# v2_2_lux.net
KiCad netlist of a schematic drawn in EAGLE
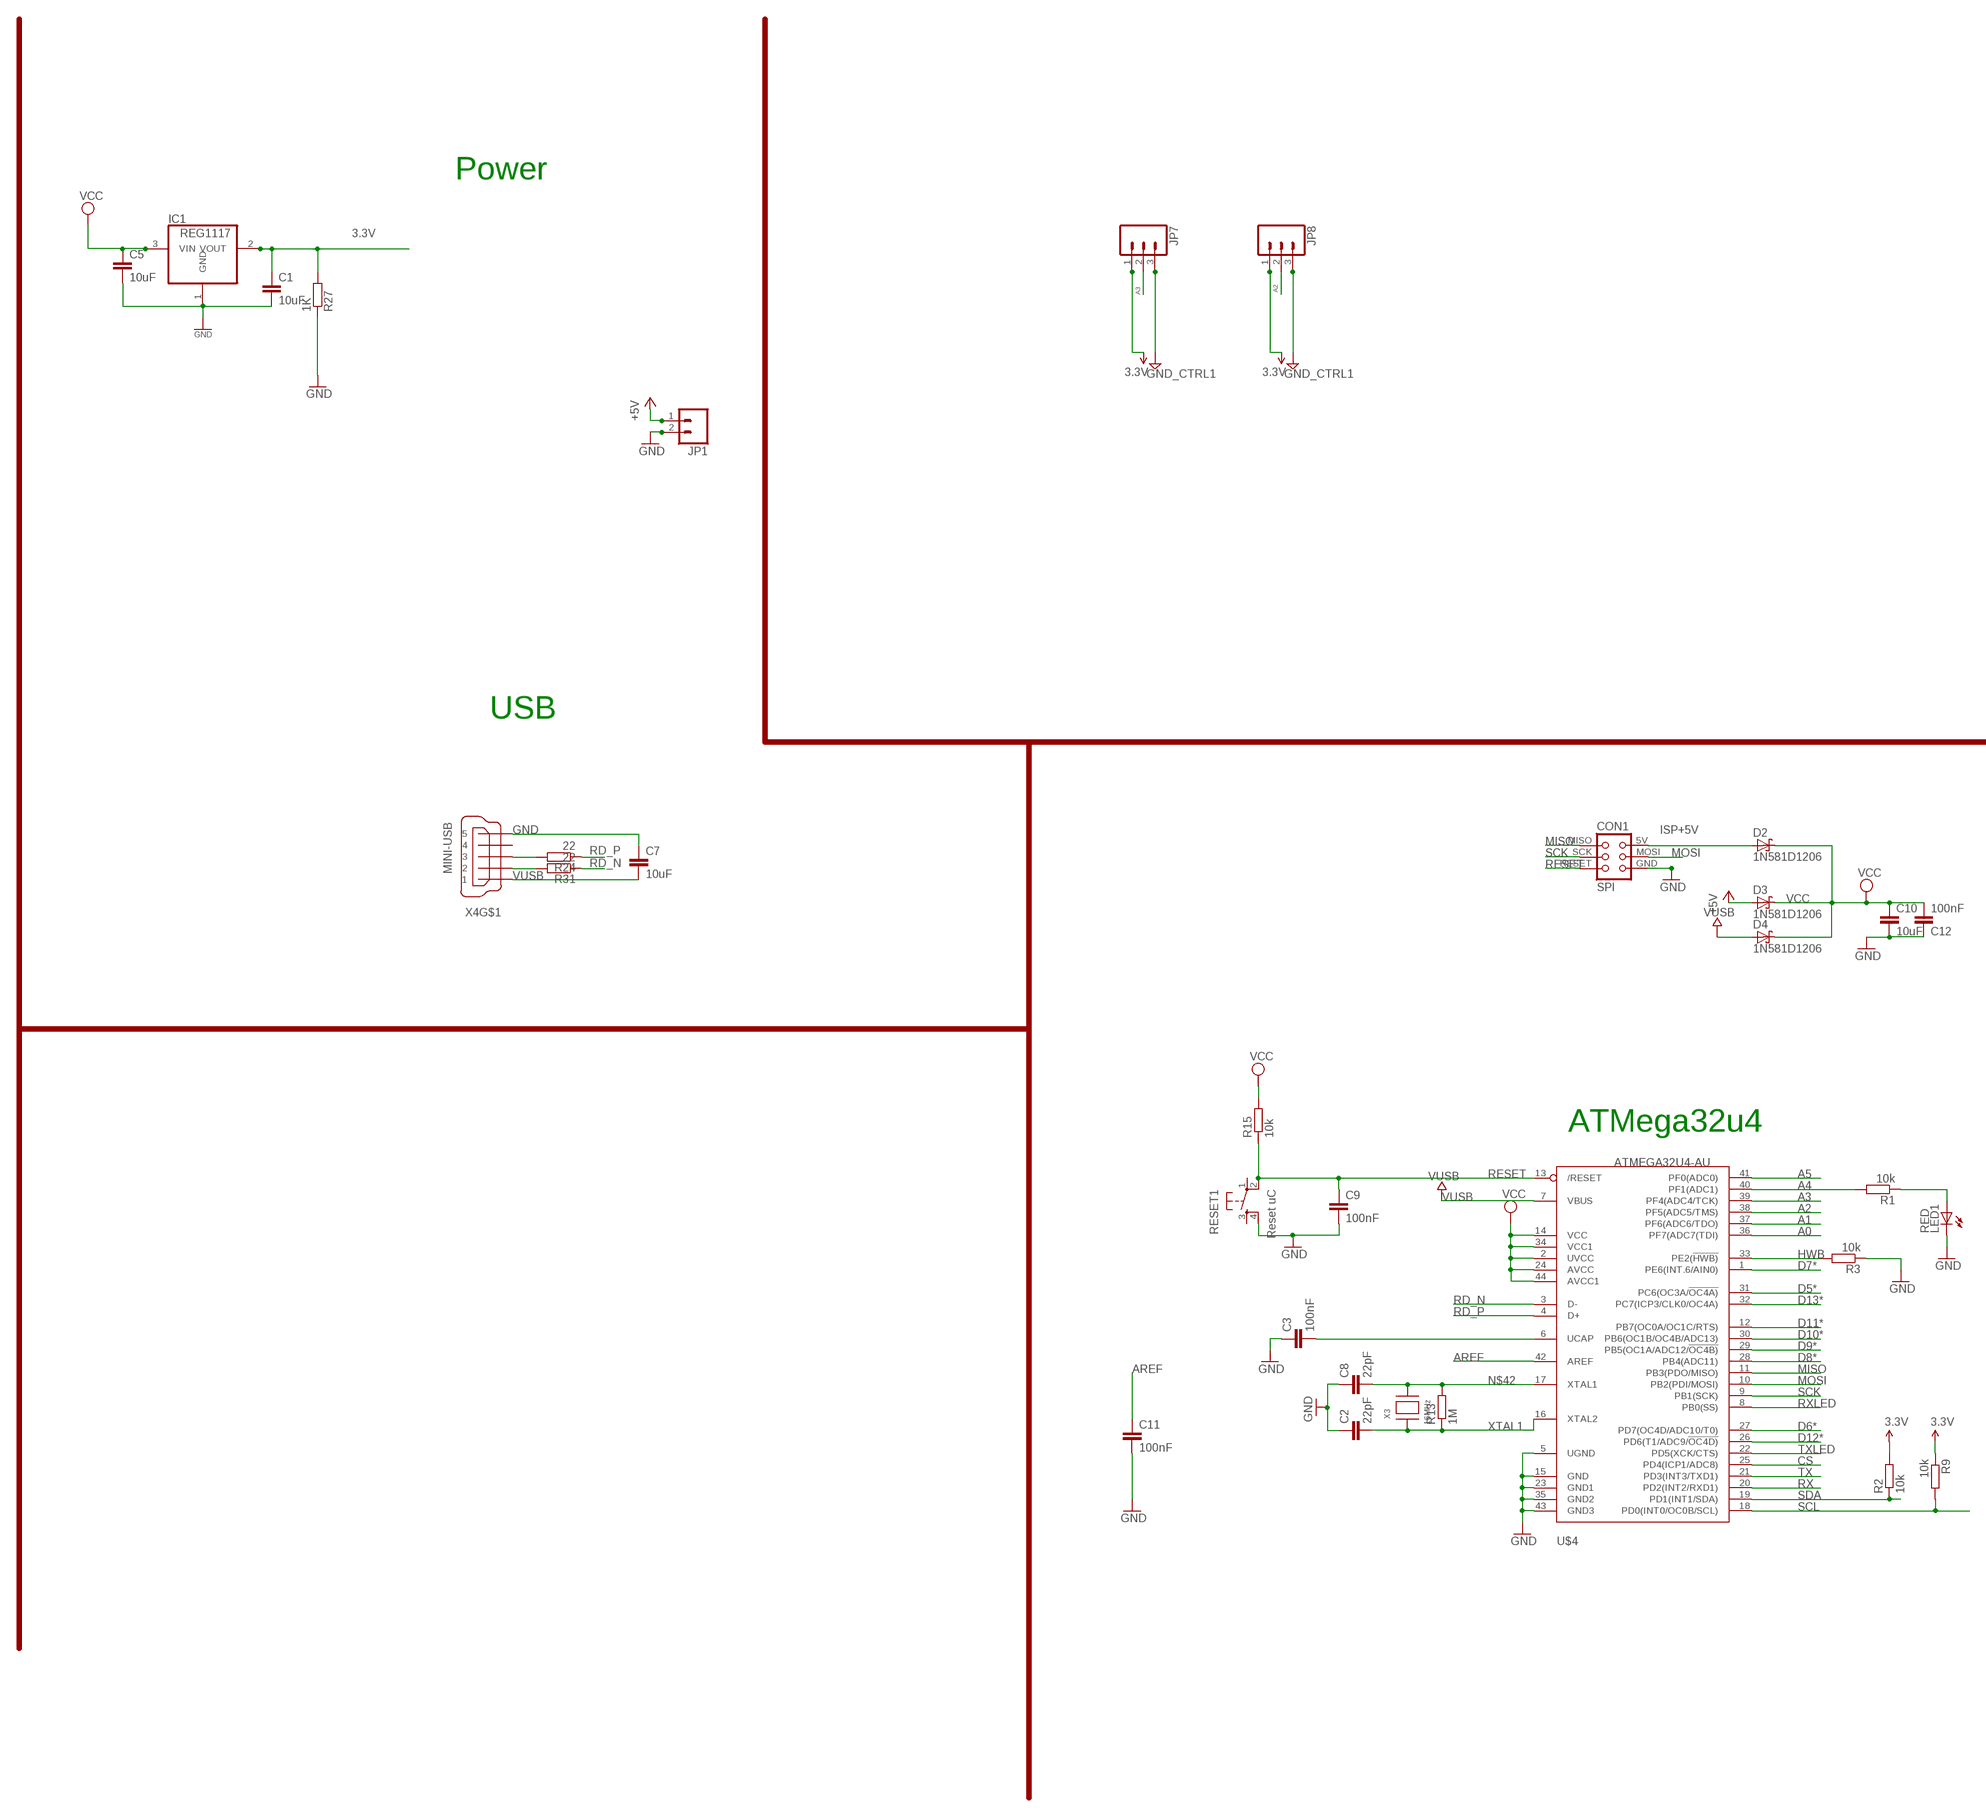
[diagram p0: schematic, sheet 1, part 1 of 2]
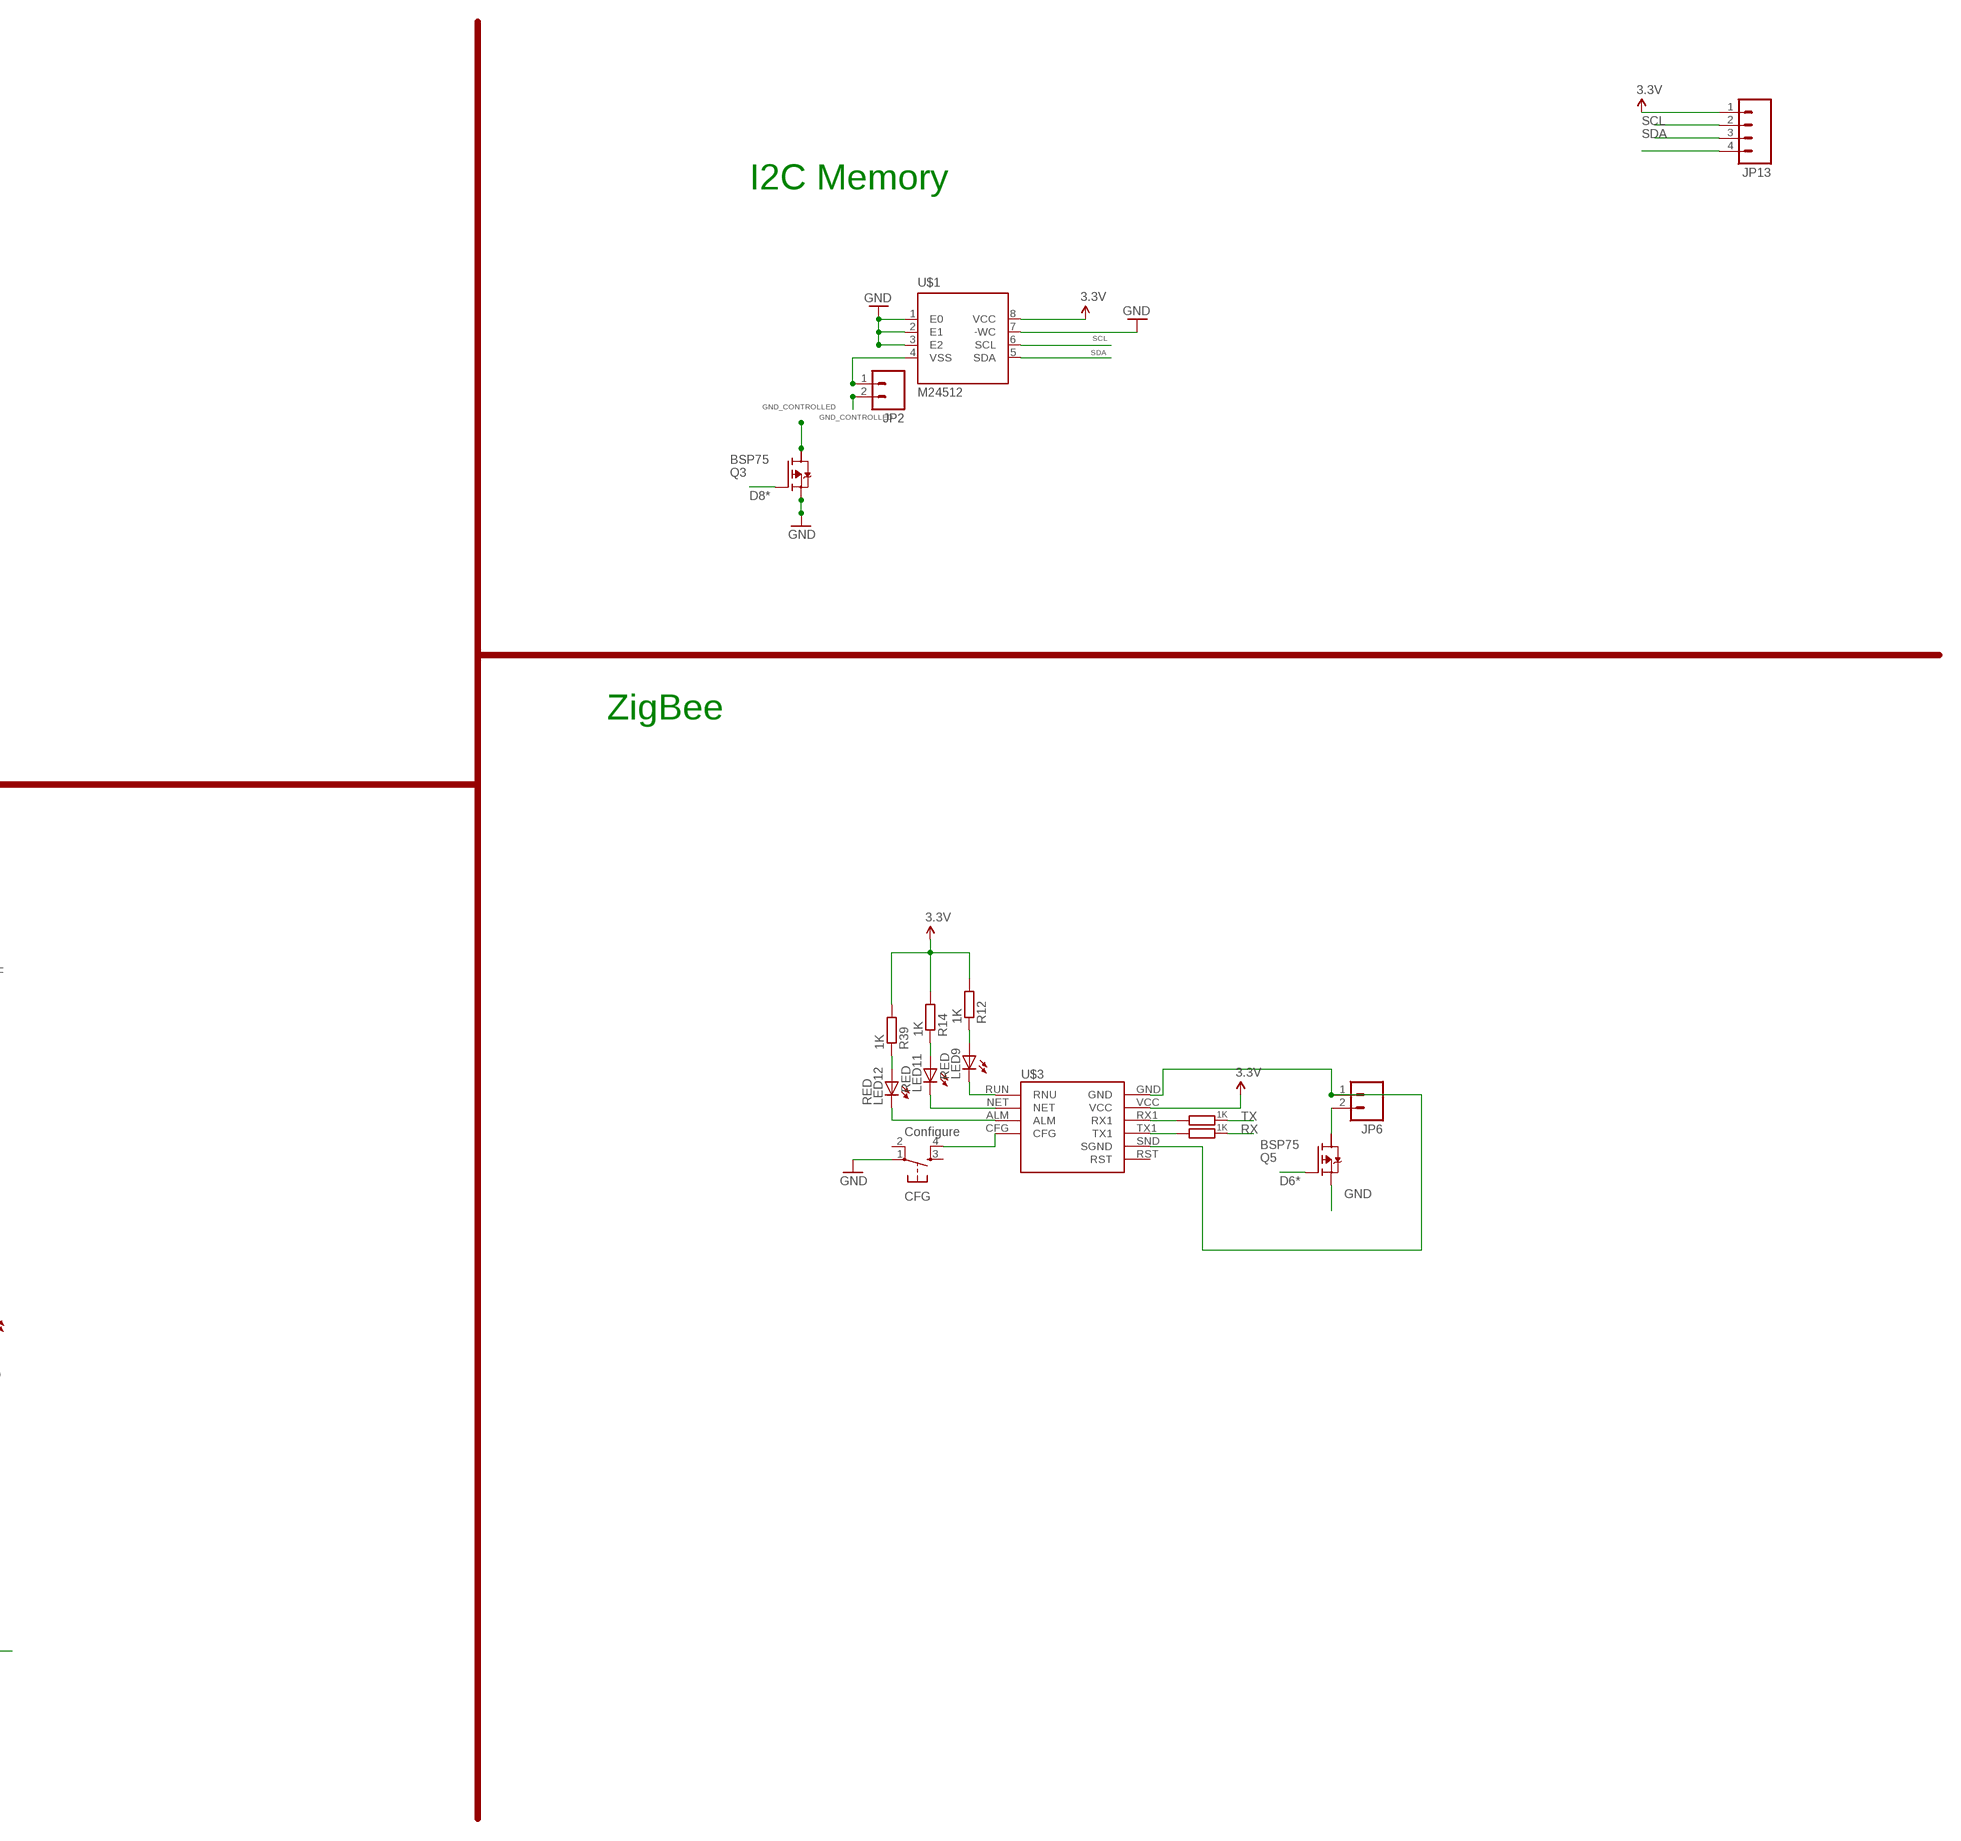
[diagram p1: schematic, sheet 1, part 2 of 2]

(export (version "E")
  (design (tool "Eeschema 10.0.6"))
  (components
    (comp (ref "C1")
      (value "10uF")
      (footprint "eagle-import:C1206")
      (libsource (lib "eagle-import") (part "C-EUC1206"))
    )
    (comp (ref "C2")
      (value "22pF")
      (footprint "eagle-import:C1206")
      (libsource (lib "eagle-import") (part "C-EUC1206"))
    )
    (comp (ref "C3")
      (value "100nF")
      (footprint "eagle-import:C1206")
      (libsource (lib "eagle-import") (part "C-EUC1206"))
    )
    (comp (ref "C5")
      (value "10uF")
      (footprint "eagle-import:C1206")
      (libsource (lib "eagle-import") (part "C-EUC1206"))
    )
    (comp (ref "C7")
      (value "10uF")
      (footprint "eagle-import:C1206")
      (libsource (lib "eagle-import") (part "C-EUC1206"))
    )
    (comp (ref "C8")
      (value "22pF")
      (footprint "eagle-import:C1206")
      (libsource (lib "eagle-import") (part "C-EUC1206"))
    )
    (comp (ref "C9")
      (value "100nF")
      (footprint "eagle-import:C1206")
      (libsource (lib "eagle-import") (part "C-EUC1206"))
    )
    (comp (ref "C10")
      (value "10uF")
      (footprint "eagle-import:C1206")
      (libsource (lib "eagle-import") (part "C-EUC1206"))
    )
    (comp (ref "C11")
      (value "100nF")
      (footprint "eagle-import:C1206")
      (libsource (lib "eagle-import") (part "C-EUC1206"))
    )
    (comp (ref "C12")
      (value "100nF")
      (footprint "eagle-import:C1206")
      (libsource (lib "eagle-import") (part "C-EUC1206"))
    )
    (comp (ref "CFG")
      (value "Configure")
      (footprint "eagle-import:TACTILE_SWITCH_SMD")
      (libsource (lib "eagle-import") (part "TAC_SWITCHSMD"))
    )
    (comp (ref "CON1")
      (value "SPI")
      (footprint "eagle-import:TC2030-MCP-NL")
      (libsource (lib "eagle-import") (part "TINYISPT"))
    )
    (comp (ref "D2")
      (value "1N581D1206")
      (footprint "eagle-import:LED-1206")
      (libsource (lib "eagle-import") (part "1N581D1206"))
    )
    (comp (ref "D3")
      (value "1N581D1206")
      (footprint "eagle-import:LED-1206")
      (libsource (lib "eagle-import") (part "1N581D1206"))
    )
    (comp (ref "D4")
      (value "1N581D1206")
      (footprint "eagle-import:LED-1206")
      (libsource (lib "eagle-import") (part "1N581D1206"))
    )
    (comp (ref "IC1")
      (value "REG1117")
      (footprint "eagle-import:SOT223")
      (libsource (lib "eagle-import") (part "REG1117"))
    )
    (comp (ref "JP1")
      (value "M02LOCK_LONGPADS")
      (footprint "eagle-import:1X02_LOCK_LONGPADS")
      (libsource (lib "eagle-import") (part "M02LOCK_LONGPADS"))
    )
    (comp (ref "JP2")
      (value "M02LOCK_LONGPADS")
      (footprint "eagle-import:1X02_LOCK_LONGPADS")
      (libsource (lib "eagle-import") (part "M02LOCK_LONGPADS"))
    )
    (comp (ref "JP6")
      (value "M02LOCK_LONGPADS")
      (footprint "eagle-import:1X02_LOCK_LONGPADS")
      (libsource (lib "eagle-import") (part "M02LOCK_LONGPADS"))
    )
    (comp (ref "JP7")
      (value "M03LONGPADS")
      (footprint "eagle-import:1X03_LONGPADS")
      (libsource (lib "eagle-import") (part "M03LONGPADS"))
    )
    (comp (ref "JP8")
      (value "M03LONGPADS")
      (footprint "eagle-import:1X03_LONGPADS")
      (libsource (lib "eagle-import") (part "M03LONGPADS"))
    )
    (comp (ref "JP13")
      (value "M04LOCK_LONGPADS")
      (footprint "eagle-import:1X04_LOCK_LONGPADS")
      (libsource (lib "eagle-import") (part "M04LOCK_LONGPADS"))
    )
    (comp (ref "LED1")
      (value "RED")
      (footprint "eagle-import:CHIP-LED0805")
      (libsource (lib "eagle-import") (part "LEDCHIP-LED0805"))
    )
    (comp (ref "LED9")
      (value "RED")
      (footprint "eagle-import:CHIP-LED0805")
      (libsource (lib "eagle-import") (part "LEDCHIP-LED0805"))
    )
    (comp (ref "LED11")
      (value "RED")
      (footprint "eagle-import:CHIP-LED0805")
      (libsource (lib "eagle-import") (part "LEDCHIP-LED0805"))
    )
    (comp (ref "LED12")
      (value "RED")
      (footprint "eagle-import:CHIP-LED0805")
      (libsource (lib "eagle-import") (part "LEDCHIP-LED0805"))
    )
    (comp (ref "Q3")
      (value "BSP75")
      (footprint "eagle-import:PG-SOT-223")
      (libsource (lib "eagle-import") (part "BSP613P"))
    )
    (comp (ref "Q5")
      (value "BSP75")
      (footprint "eagle-import:PG-SOT-223")
      (libsource (lib "eagle-import") (part "BSP613P"))
    )
    (comp (ref "R1")
      (value "10k")
      (footprint "eagle-import:M1206")
      (libsource (lib "eagle-import") (part "resistor_R-EU_M1206"))
    )
    (comp (ref "R2")
      (value "10k")
      (footprint "eagle-import:M1206")
      (libsource (lib "eagle-import") (part "resistor_R-EU_M1206"))
    )
    (comp (ref "R3")
      (value "10k")
      (footprint "eagle-import:M1206")
      (libsource (lib "eagle-import") (part "resistor_R-EU_M1206"))
    )
    (comp (ref "R8")
      (value "1K")
      (footprint "eagle-import:R0805")
      (libsource (lib "eagle-import") (part "R-EU_R0805"))
    )
    (comp (ref "R9")
      (value "10k")
      (footprint "eagle-import:M1206")
      (libsource (lib "eagle-import") (part "resistor_R-EU_M1206"))
    )
    (comp (ref "R11")
      (value "1K")
      (footprint "eagle-import:R0805")
      (libsource (lib "eagle-import") (part "R-EU_R0805"))
    )
    (comp (ref "R12")
      (value "1K")
      (footprint "eagle-import:R0805")
      (libsource (lib "eagle-import") (part "R-EU_R0805"))
    )
    (comp (ref "R13")
      (value "1M")
      (footprint "eagle-import:R1206")
      (libsource (lib "eagle-import") (part "R-EU_R1206"))
    )
    (comp (ref "R14")
      (value "1K")
      (footprint "eagle-import:R0805")
      (libsource (lib "eagle-import") (part "R-EU_R0805"))
    )
    (comp (ref "R15")
      (value "10k")
      (footprint "eagle-import:M0805")
      (libsource (lib "eagle-import") (part "resistor_R-EU_M0805"))
    )
    (comp (ref "R24")
      (value "22")
      (footprint "eagle-import:M1206")
      (libsource (lib "eagle-import") (part "resistor_R-EU_M1206"))
    )
    (comp (ref "R27")
      (value "1K")
      (footprint "eagle-import:R0805")
      (libsource (lib "eagle-import") (part "R-EU_R0805"))
    )
    (comp (ref "R31")
      (value "22")
      (footprint "eagle-import:M1206")
      (libsource (lib "eagle-import") (part "resistor_R-EU_M1206"))
    )
    (comp (ref "R39")
      (value "1K")
      (footprint "eagle-import:R0805")
      (libsource (lib "eagle-import") (part "R-EU_R0805"))
    )
    (comp (ref "RESET1")
      (value "Reset uC")
      (footprint "eagle-import:TACTILE_SWITCH_SMD")
      (libsource (lib "eagle-import") (part "TAC_SWITCHSMD"))
    )
    (comp (ref "U$1")
      (value "M24512")
      (footprint "eagle-import:SO8")
      (libsource (lib "eagle-import") (part "M24512"))
    )
    (comp (ref "U$3")
      (value "SZ05-ZIGBEETHROUGHHOLE")
      (footprint "eagle-import:SZ05-ZIGBEE4")
      (libsource (lib "eagle-import") (part "SZ05-ZIGBEETHROUGHHOLE"))
    )
    (comp (ref "U$4")
      (value "ATMEGA32U4-AU")
      (footprint "eagle-import:TQFP44")
      (libsource (lib "eagle-import") (part "ATMEGA32U4-AU"))
    )
    (comp (ref "X3")
      (value "16MHz")
      (footprint "eagle-import:NX6035")
      (libsource (lib "eagle-import") (part "XTALNX6035"))
    )
    (comp (ref "X4")
      (value "MINI-USB")
      (footprint "eagle-import:32005-201")
      (libsource (lib "eagle-import") (part "MINI-USB-SCHIELD-32005-201"))
    )
  )
  (nets
    (net (code "1") (name "+5V") (class "Default")
      (node (ref "D3") (pin "A") (pinfunction "A_A") (pintype "passive"))
      (node (ref "JP1") (pin "1") (pinfunction "1_1") (pintype "passive"))
    )
    (net (code "2") (name "/A0") (class "Default")
      (node (ref "U$4") (pin "36") (pinfunction "PF7(ADC7(TDI)_36") (pintype "bidirectional"))
    )
    (net (code "3") (name "/A1") (class "Default")
      (node (ref "U$4") (pin "37") (pinfunction "PF6(ADC6/TDO)_37") (pintype "bidirectional"))
    )
    (net (code "4") (name "/A2") (class "Default")
      (node (ref "JP8") (pin "2") (pinfunction "2_2") (pintype "passive"))
      (node (ref "U$4") (pin "38") (pinfunction "PF5(ADC5/TMS)_38") (pintype "bidirectional"))
    )
    (net (code "5") (name "/A3") (class "Default")
      (node (ref "JP7") (pin "2") (pinfunction "2_2") (pintype "passive"))
      (node (ref "U$4") (pin "39") (pinfunction "PF4(ADC4/TCK)_39") (pintype "bidirectional"))
    )
    (net (code "6") (name "/A4") (class "Default")
      (node (ref "R1") (pin "2") (pinfunction "2_2") (pintype "passive"))
      (node (ref "U$4") (pin "40") (pinfunction "PF1(ADC1)_40") (pintype "bidirectional"))
    )
    (net (code "7") (name "/A5") (class "Default")
      (node (ref "U$4") (pin "41") (pinfunction "PF0(ADC0)_41") (pintype "bidirectional"))
    )
    (net (code "8") (name "/AREF") (class "Default")
      (node (ref "C11") (pin "1") (pinfunction "1_1") (pintype "passive"))
      (node (ref "U$4") (pin "42") (pinfunction "AREF_42") (pintype "bidirectional"))
    )
    (net (code "9") (name "/CS") (class "Default")
      (node (ref "U$4") (pin "25") (pinfunction "PD4(ICP1/ADC8)_25") (pintype "bidirectional"))
    )
    (net (code "10") (name "/D5*") (class "Default")
      (node (ref "U$4") (pin "31") (pinfunction "PC6(OC3A/~{OC4A})_31") (pintype "bidirectional"))
    )
    (net (code "11") (name "/D6*") (class "Default")
      (node (ref "Q5") (pin "1") (pinfunction "G_1") (pintype "passive"))
      (node (ref "U$4") (pin "27") (pinfunction "PD7(OC4D/ADC10/T0)_27") (pintype "bidirectional"))
    )
    (net (code "12") (name "/D7*") (class "Default")
      (node (ref "U$4") (pin "1") (pinfunction "PE6(INT.6/AIN0)_1") (pintype "bidirectional"))
    )
    (net (code "13") (name "/D8*") (class "Default")
      (node (ref "Q3") (pin "1") (pinfunction "G_1") (pintype "passive"))
      (node (ref "U$4") (pin "28") (pinfunction "PB4(ADC11)_28") (pintype "bidirectional"))
    )
    (net (code "14") (name "/D9*") (class "Default")
      (node (ref "U$4") (pin "29") (pinfunction "PB5(OC1A/ADC12/~{OC4B})_29") (pintype "bidirectional"))
    )
    (net (code "15") (name "/D10*") (class "Default")
      (node (ref "U$4") (pin "30") (pinfunction "PB6(OC1B/OC4B/ADC13)_30") (pintype "bidirectional"))
    )
    (net (code "16") (name "/D11*") (class "Default")
      (node (ref "U$4") (pin "12") (pinfunction "PB7(OC0A/OC1C/RTS)_12") (pintype "bidirectional"))
    )
    (net (code "17") (name "/D12*") (class "Default")
      (node (ref "U$4") (pin "26") (pinfunction "PD6(T1/ADC9/~{OC4D})_26") (pintype "bidirectional"))
    )
    (net (code "18") (name "/D13*") (class "Default")
      (node (ref "U$4") (pin "32") (pinfunction "PC7(ICP3/CLK0/OC4A)_32") (pintype "bidirectional"))
    )
    (net (code "19") (name "/GND_CONTROLLED") (class "Default")
      (node (ref "JP13") (pin "4") (pinfunction "4_4") (pintype "passive"))
      (node (ref "JP2") (pin "2") (pinfunction "2_2") (pintype "passive"))
      (node (ref "Q3") (pin "2") (pinfunction "D_2") (pintype "passive"))
    )
    (net (code "20") (name "/HWB") (class "Default")
      (node (ref "R3") (pin "2") (pinfunction "2_2") (pintype "passive"))
      (node (ref "U$4") (pin "33") (pinfunction "PE2(~{HWB})_33") (pintype "bidirectional"))
    )
    (net (code "21") (name "/ISP+5V") (class "Default")
      (node (ref "CON1") (pin "5V") (pinfunction "VCC_5V") (pintype "passive"))
      (node (ref "D2") (pin "A") (pinfunction "A_A") (pintype "passive"))
    )
    (net (code "22") (name "/MISO") (class "Default")
      (node (ref "CON1") (pin "MISO") (pinfunction "MISO_MISO") (pintype "passive"))
      (node (ref "U$4") (pin "11") (pinfunction "PB3(PDO/MISO)_11") (pintype "bidirectional"))
    )
    (net (code "23") (name "/MOSI") (class "Default")
      (node (ref "CON1") (pin "MOSI") (pinfunction "MOSI_MOSI") (pintype "passive"))
      (node (ref "U$4") (pin "10") (pinfunction "PB2(PDI/MOSI)_10") (pintype "bidirectional"))
    )
    (net (code "24") (name "/N$42") (class "Default")
      (node (ref "C8") (pin "2") (pinfunction "2_2") (pintype "passive"))
      (node (ref "R13") (pin "2") (pinfunction "2_2") (pintype "passive"))
      (node (ref "U$4") (pin "17") (pinfunction "XTAL1_17") (pintype "bidirectional"))
      (node (ref "X3") (pin "P$2") (pinfunction "P$2_P$2") (pintype "bidirectional"))
    )
    (net (code "25") (name "/RD_N") (class "Default")
      (node (ref "R31") (pin "1") (pinfunction "1_1") (pintype "passive"))
      (node (ref "U$4") (pin "3") (pinfunction "D-_3") (pintype "bidirectional"))
    )
    (net (code "26") (name "/RD_P") (class "Default")
      (node (ref "R24") (pin "1") (pinfunction "1_1") (pintype "passive"))
      (node (ref "U$4") (pin "4") (pinfunction "D+_4") (pintype "bidirectional"))
    )
    (net (code "27") (name "/RESET") (class "Default")
      (node (ref "C9") (pin "1") (pinfunction "1_1") (pintype "passive"))
      (node (ref "CON1") (pin "RESET") (pinfunction "RESET_RESET") (pintype "passive"))
      (node (ref "R15") (pin "1") (pinfunction "1_1") (pintype "passive"))
      (node (ref "RESET1") (pin "2") (pinfunction "2_2") (pintype "passive"))
      (node (ref "U$4") (pin "13") (pinfunction "/RESET_13") (pintype "bidirectional"))
    )
    (net (code "28") (name "/RX") (class "Default")
      (node (ref "R8") (pin "1") (pinfunction "1_1") (pintype "passive"))
      (node (ref "U$4") (pin "20") (pinfunction "PD2(INT2/RXD1)_20") (pintype "bidirectional"))
    )
    (net (code "29") (name "/RXLED") (class "Default")
      (node (ref "U$4") (pin "8") (pinfunction "PB0(SS)_8") (pintype "bidirectional"))
    )
    (net (code "30") (name "/SCK") (class "Default")
      (node (ref "CON1") (pin "SCK") (pinfunction "SCK_SCK") (pintype "passive"))
      (node (ref "U$4") (pin "9") (pinfunction "PB1(SCK)_9") (pintype "bidirectional"))
    )
    (net (code "31") (name "/SCL") (class "Default")
      (node (ref "JP13") (pin "2") (pinfunction "2_2") (pintype "passive"))
      (node (ref "R9") (pin "2") (pinfunction "2_2") (pintype "passive"))
      (node (ref "U$1") (pin "6") (pinfunction "SCL_6") (pintype "bidirectional"))
      (node (ref "U$4") (pin "18") (pinfunction "PD0(INT0/OC0B/SCL)_18") (pintype "bidirectional"))
    )
    (net (code "32") (name "/SDA") (class "Default")
      (node (ref "JP13") (pin "3") (pinfunction "3_3") (pintype "passive"))
      (node (ref "R2") (pin "1") (pinfunction "1_1") (pintype "passive"))
      (node (ref "U$1") (pin "5") (pinfunction "SDA_5") (pintype "bidirectional"))
      (node (ref "U$4") (pin "19") (pinfunction "PD1(INT1/SDA)_19") (pintype "bidirectional"))
    )
    (net (code "33") (name "/TX") (class "Default")
      (node (ref "R11") (pin "1") (pinfunction "1_1") (pintype "passive"))
      (node (ref "U$4") (pin "21") (pinfunction "PD3(INT3/TXD1)_21") (pintype "bidirectional"))
    )
    (net (code "34") (name "/TXLED") (class "Default")
      (node (ref "U$4") (pin "22") (pinfunction "PD5(XCK/CTS)_22") (pintype "bidirectional"))
    )
    (net (code "35") (name "/XTAL1") (class "Default")
      (node (ref "C2") (pin "2") (pinfunction "2_2") (pintype "passive"))
      (node (ref "R13") (pin "1") (pinfunction "1_1") (pintype "passive"))
      (node (ref "U$4") (pin "16") (pinfunction "XTAL2_16") (pintype "bidirectional"))
      (node (ref "X3") (pin "P$1") (pinfunction "P$1_P$1") (pintype "bidirectional"))
    )
    (net (code "36") (name "3.3V") (class "Default")
      (node (ref "C1") (pin "1") (pinfunction "1_1") (pintype "passive"))
      (node (ref "IC1") (pin "2") (pinfunction "VOUT_2") (pintype "output"))
      (node (ref "JP13") (pin "1") (pinfunction "1_1") (pintype "passive"))
      (node (ref "JP7") (pin "1") (pinfunction "1_1") (pintype "passive"))
      (node (ref "JP8") (pin "1") (pinfunction "1_1") (pintype "passive"))
      (node (ref "R12") (pin "2") (pinfunction "2_2") (pintype "passive"))
      (node (ref "R14") (pin "2") (pinfunction "2_2") (pintype "passive"))
      (node (ref "R2") (pin "2") (pinfunction "2_2") (pintype "passive"))
      (node (ref "R27") (pin "2") (pinfunction "2_2") (pintype "passive"))
      (node (ref "R39") (pin "2") (pinfunction "2_2") (pintype "passive"))
      (node (ref "R9") (pin "1") (pinfunction "1_1") (pintype "passive"))
      (node (ref "U$1") (pin "8") (pinfunction "VCC_8") (pintype "power_in"))
      (node (ref "U$3") (pin "VCC") (pinfunction "VCC_VCC") (pintype "bidirectional"))
    )
    (net (code "37") (name "GND") (class "Default")
      (node (ref "C1") (pin "2") (pinfunction "2_2") (pintype "passive"))
      (node (ref "C10") (pin "2") (pinfunction "2_2") (pintype "passive"))
      (node (ref "C11") (pin "2") (pinfunction "2_2") (pintype "passive"))
      (node (ref "C12") (pin "1") (pinfunction "1_1") (pintype "passive"))
      (node (ref "C2") (pin "1") (pinfunction "1_1") (pintype "passive"))
      (node (ref "C3") (pin "1") (pinfunction "1_1") (pintype "passive"))
      (node (ref "C5") (pin "2") (pinfunction "2_2") (pintype "passive"))
      (node (ref "C7") (pin "1") (pinfunction "1_1") (pintype "passive"))
      (node (ref "C8") (pin "1") (pinfunction "1_1") (pintype "passive"))
      (node (ref "C9") (pin "2") (pinfunction "2_2") (pintype "passive"))
      (node (ref "CFG") (pin "1") (pinfunction "1_1") (pintype "passive"))
      (node (ref "CON1") (pin "GND") (pinfunction "GND_GND") (pintype "passive"))
      (node (ref "IC1") (pin "1") (pinfunction "GND_1") (pintype "power_in"))
      (node (ref "JP1") (pin "2") (pinfunction "2_2") (pintype "passive"))
      (node (ref "JP7") (pin "3") (pinfunction "3_3") (pintype "passive"))
      (node (ref "JP8") (pin "3") (pinfunction "3_3") (pintype "passive"))
      (node (ref "LED1") (pin "C") (pinfunction "C_C") (pintype "passive"))
      (node (ref "Q3") (pin "3") (pinfunction "S_3") (pintype "passive"))
      (node (ref "Q5") (pin "3") (pinfunction "S_3") (pintype "passive"))
      (node (ref "R27") (pin "1") (pinfunction "1_1") (pintype "passive"))
      (node (ref "R3") (pin "1") (pinfunction "1_1") (pintype "passive"))
      (node (ref "RESET1") (pin "4") (pinfunction "4_4") (pintype "passive"))
      (node (ref "U$1") (pin "1") (pinfunction "E0_1") (pintype "bidirectional"))
      (node (ref "U$1") (pin "2") (pinfunction "E1_2") (pintype "bidirectional"))
      (node (ref "U$1") (pin "3") (pinfunction "E2_3") (pintype "bidirectional"))
      (node (ref "U$1") (pin "7") (pinfunction "-WC_7") (pintype "bidirectional"))
      (node (ref "U$4") (pin "15") (pinfunction "GND_15") (pintype "bidirectional"))
      (node (ref "U$4") (pin "23") (pinfunction "GND1_23") (pintype "bidirectional"))
      (node (ref "U$4") (pin "35") (pinfunction "GND2_35") (pintype "bidirectional"))
      (node (ref "U$4") (pin "43") (pinfunction "GND3_43") (pintype "bidirectional"))
      (node (ref "U$4") (pin "5") (pinfunction "UGND_5") (pintype "bidirectional"))
      (node (ref "X4") (pin "5") (pinfunction "5_5") (pintype "passive"))
    )
    (net (code "38") (name "Net-(CFG-Pad4)") (class "Default")
      (node (ref "CFG") (pin "4") (pinfunction "4_4") (pintype "passive"))
      (node (ref "U$3") (pin "CFG") (pinfunction "CFG_CFG") (pintype "bidirectional"))
    )
    (net (code "39") (name "Net-(JP6-Pad2)") (class "Default")
      (node (ref "JP6") (pin "2") (pinfunction "2_2") (pintype "passive"))
      (node (ref "Q5") (pin "2") (pinfunction "D_2") (pintype "passive"))
    )
    (net (code "40") (name "Net-(LED1-PadA)") (class "Default")
      (node (ref "LED1") (pin "A") (pinfunction "A_A") (pintype "passive"))
      (node (ref "R1") (pin "1") (pinfunction "1_1") (pintype "passive"))
    )
    (net (code "41") (name "Net-(LED9-PadA)") (class "Default")
      (node (ref "LED9") (pin "A") (pinfunction "A_A") (pintype "passive"))
      (node (ref "R12") (pin "1") (pinfunction "1_1") (pintype "passive"))
    )
    (net (code "42") (name "Net-(LED11-PadA)") (class "Default")
      (node (ref "LED11") (pin "A") (pinfunction "A_A") (pintype "passive"))
      (node (ref "R14") (pin "1") (pinfunction "1_1") (pintype "passive"))
    )
    (net (code "43") (name "Net-(LED11-PadC)") (class "Default")
      (node (ref "LED11") (pin "C") (pinfunction "C_C") (pintype "passive"))
      (node (ref "U$3") (pin "NET") (pinfunction "NET_NET") (pintype "bidirectional"))
    )
    (net (code "44") (name "Net-(LED12-PadA)") (class "Default")
      (node (ref "LED12") (pin "A") (pinfunction "A_A") (pintype "passive"))
      (node (ref "R39") (pin "1") (pinfunction "1_1") (pintype "passive"))
    )
    (net (code "45") (name "Net-(LED12-PadC)") (class "Default")
      (node (ref "LED12") (pin "C") (pinfunction "C_C") (pintype "passive"))
      (node (ref "U$3") (pin "ALM") (pinfunction "ALM_ALM") (pintype "bidirectional"))
    )
    (net (code "46") (name "Net-(R8-Pad2)") (class "Default")
      (node (ref "R8") (pin "2") (pinfunction "2_2") (pintype "passive"))
      (node (ref "U$3") (pin "TX1") (pinfunction "TX1_TX1") (pintype "bidirectional"))
    )
    (net (code "47") (name "Net-(R11-Pad2)") (class "Default")
      (node (ref "R11") (pin "2") (pinfunction "2_2") (pintype "passive"))
      (node (ref "U$3") (pin "RX1") (pinfunction "RX1_RX1") (pintype "bidirectional"))
    )
    (net (code "48") (name "Net-(R24-Pad2)") (class "Default")
      (node (ref "R24") (pin "2") (pinfunction "2_2") (pintype "passive"))
      (node (ref "X4") (pin "3") (pinfunction "3_3") (pintype "passive"))
    )
    (net (code "49") (name "Net-(R31-Pad2)") (class "Default")
      (node (ref "R31") (pin "2") (pinfunction "2_2") (pintype "passive"))
      (node (ref "X4") (pin "2") (pinfunction "2_2") (pintype "passive"))
    )
    (net (code "50") (name "Net-(U$1-VSS)") (class "Default")
      (node (ref "JP2") (pin "1") (pinfunction "1_1") (pintype "passive"))
      (node (ref "U$1") (pin "4") (pinfunction "VSS_4") (pintype "power_in"))
    )
    (net (code "51") (name "Net-(U$3-RNU)") (class "Default")
      (node (ref "LED9") (pin "C") (pinfunction "C_C") (pintype "passive"))
      (node (ref "U$3") (pin "RUN") (pinfunction "RNU_RUN") (pintype "bidirectional"))
    )
    (net (code "52") (name "Net-(U$3-SGND)") (class "Default")
      (node (ref "JP6") (pin "1") (pinfunction "1_1") (pintype "passive"))
      (node (ref "U$3") (pin "GND") (pinfunction "GND_GND") (pintype "bidirectional"))
      (node (ref "U$3") (pin "SND") (pinfunction "SGND_SND") (pintype "bidirectional"))
    )
    (net (code "53") (name "Net-(U$4-UCAP)") (class "Default")
      (node (ref "C3") (pin "2") (pinfunction "2_2") (pintype "passive"))
      (node (ref "U$4") (pin "6") (pinfunction "UCAP_6") (pintype "bidirectional"))
    )
    (net (code "54") (name "VCC") (class "Default")
      (node (ref "C10") (pin "1") (pinfunction "1_1") (pintype "passive"))
      (node (ref "C12") (pin "2") (pinfunction "2_2") (pintype "passive"))
      (node (ref "C5") (pin "1") (pinfunction "1_1") (pintype "passive"))
      (node (ref "D2") (pin "C") (pinfunction "C_C") (pintype "passive"))
      (node (ref "D3") (pin "C") (pinfunction "C_C") (pintype "passive"))
      (node (ref "D4") (pin "C") (pinfunction "C_C") (pintype "passive"))
      (node (ref "IC1") (pin "3") (pinfunction "VIN_3") (pintype "input"))
      (node (ref "R15") (pin "2") (pinfunction "2_2") (pintype "passive"))
      (node (ref "U$4") (pin "14") (pinfunction "VCC_14") (pintype "bidirectional"))
      (node (ref "U$4") (pin "2") (pinfunction "UVCC_2") (pintype "bidirectional"))
      (node (ref "U$4") (pin "24") (pinfunction "AVCC_24") (pintype "bidirectional"))
      (node (ref "U$4") (pin "34") (pinfunction "VCC1_34") (pintype "bidirectional"))
      (node (ref "U$4") (pin "44") (pinfunction "AVCC1_44") (pintype "bidirectional"))
    )
    (net (code "55") (name "VUSB") (class "Default")
      (node (ref "C7") (pin "2") (pinfunction "2_2") (pintype "passive"))
      (node (ref "D4") (pin "A") (pinfunction "A_A") (pintype "passive"))
      (node (ref "U$4") (pin "7") (pinfunction "VBUS_7") (pintype "bidirectional"))
      (node (ref "X4") (pin "1") (pinfunction "1_1") (pintype "passive"))
    )
    (net (code "56") (name "unconnected-(CFG-Pad2)") (class "Default")
      (node (ref "CFG") (pin "2") (pinfunction "2_2") (pintype "passive"))
    )
    (net (code "57") (name "unconnected-(CFG-Pad3)") (class "Default")
      (node (ref "CFG") (pin "3") (pinfunction "3_3") (pintype "passive"))
    )
    (net (code "58") (name "unconnected-(Q3-D-Pad4)") (class "Default")
      (node (ref "Q3") (pin "4") (pinfunction "D_4") (pintype "passive"))
    )
    (net (code "59") (name "unconnected-(Q5-D-Pad4)") (class "Default")
      (node (ref "Q5") (pin "4") (pinfunction "D_4") (pintype "passive"))
    )
    (net (code "60") (name "unconnected-(RESET1-Pad1)") (class "Default")
      (node (ref "RESET1") (pin "1") (pinfunction "1_1") (pintype "passive"))
    )
    (net (code "61") (name "unconnected-(RESET1-Pad3)") (class "Default")
      (node (ref "RESET1") (pin "3") (pinfunction "3_3") (pintype "passive"))
    )
    (net (code "62") (name "unconnected-(U$3-PadRST)") (class "Default")
      (node (ref "U$3") (pin "RST") (pinfunction "RST_RST") (pintype "bidirectional"))
    )
    (net (code "63") (name "unconnected-(X4-Pad4)") (class "Default")
      (node (ref "X4") (pin "4") (pinfunction "4_4") (pintype "passive"))
    )
  )
)
